# DS12C887.net
KiCad netlist of a schematic drawn in Altium Designer
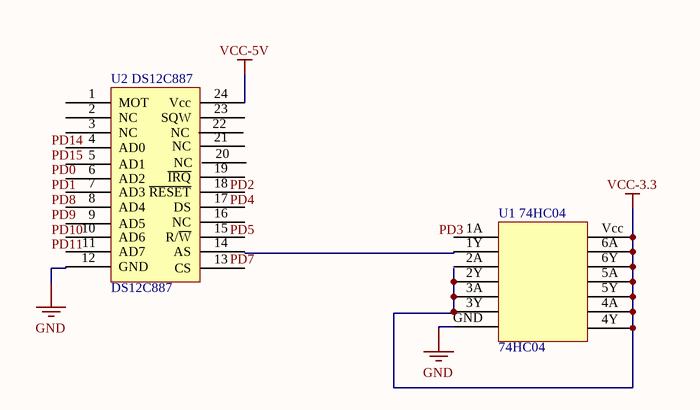
[diagram p0: DS12C887.SchDoc]

(export (version "E")
  (design (tool "Eeschema 10.0.6"))
  (components
    (comp (ref "U1 74HC04") (value "74HC04") (libsource (lib "Schlib1") (part "74HC04")))
    (comp (ref "U2 DS12C887") (value "DS12C887") (libsource (lib "Schlib1") (part "DS12C887")))
  )
  (nets
    (net (code "14") (name "GND") (class "Default")
      (node (ref "U1 74HC04") (pin "GND") (pinfunction "7_GND") (pintype "passive"))
      (node (ref "U2 DS12C887") (pin "12") (pinfunction "GND_12") (pintype "passive"))
    )
    (net (code "15") (name "VCC-3.3") (class "Default")
      (node (ref "U1 74HC04") (pin "2Y") (pinfunction "4_2Y") (pintype "passive"))
      (node (ref "U1 74HC04") (pin "3A") (pinfunction "5_3A") (pintype "passive"))
      (node (ref "U1 74HC04") (pin "3Y") (pinfunction "6_3Y") (pintype "passive"))
      (node (ref "U1 74HC04") (pin "4A") (pinfunction "9_4A") (pintype "passive"))
      (node (ref "U1 74HC04") (pin "4Y") (pinfunction "8_4Y") (pintype "passive"))
      (node (ref "U1 74HC04") (pin "5A") (pinfunction "11_5A") (pintype "passive"))
      (node (ref "U1 74HC04") (pin "5Y") (pinfunction "10_5Y") (pintype "passive"))
      (node (ref "U1 74HC04") (pin "6A") (pinfunction "13_6A") (pintype "passive"))
      (node (ref "U1 74HC04") (pin "6Y") (pinfunction "12_6Y") (pintype "passive"))
      (node (ref "U1 74HC04") (pin "Vcc") (pinfunction "14_Vcc") (pintype "passive"))
    )
    (net (code "16") (name "VCC-5V") (class "Default")
      (node (ref "U2 DS12C887") (pin "24") (pinfunction "Vcc_24") (pintype "passive"))
    )
    (net (code "17") (name "unconnected-(U1 74HC04-1-Pad1A)") (class "Default")
      (node (ref "U1 74HC04") (pin "1A") (pinfunction "1_1A") (pintype "passive"))
    )
    (net (code "18") (name "unconnected-(U1 74HC04-2-Pad1Y)") (class "Default")
      (node (ref "U1 74HC04") (pin "1Y") (pinfunction "2_1Y") (pintype "passive"))
    )
    (net (code "19") (name "unconnected-(U1 74HC04-3-Pad2A)") (class "Default")
      (node (ref "U1 74HC04") (pin "2A") (pinfunction "3_2A") (pintype "passive"))
    )
    (net (code "20") (name "unconnected-(U2 DS12C887-AD0-Pad4)") (class "Default")
      (node (ref "U2 DS12C887") (pin "4") (pinfunction "AD0_4") (pintype "passive"))
    )
    (net (code "21") (name "unconnected-(U2 DS12C887-AD1-Pad5)") (class "Default")
      (node (ref "U2 DS12C887") (pin "5") (pinfunction "AD1_5") (pintype "passive"))
    )
    (net (code "22") (name "unconnected-(U2 DS12C887-AD2-Pad6)") (class "Default")
      (node (ref "U2 DS12C887") (pin "6") (pinfunction "AD2_6") (pintype "passive"))
    )
    (net (code "23") (name "unconnected-(U2 DS12C887-AD3-Pad7)") (class "Default")
      (node (ref "U2 DS12C887") (pin "7") (pinfunction "AD3_7") (pintype "passive"))
    )
    (net (code "24") (name "unconnected-(U2 DS12C887-AD4-Pad8)") (class "Default")
      (node (ref "U2 DS12C887") (pin "8") (pinfunction "AD4_8") (pintype "passive"))
    )
    (net (code "25") (name "unconnected-(U2 DS12C887-AD5-Pad9)") (class "Default")
      (node (ref "U2 DS12C887") (pin "9") (pinfunction "AD5_9") (pintype "passive"))
    )
    (net (code "26") (name "unconnected-(U2 DS12C887-AD6-Pad10)") (class "Default")
      (node (ref "U2 DS12C887") (pin "10") (pinfunction "AD6_10") (pintype "passive"))
    )
    (net (code "27") (name "unconnected-(U2 DS12C887-AD7-Pad11)") (class "Default")
      (node (ref "U2 DS12C887") (pin "11") (pinfunction "AD7_11") (pintype "passive"))
    )
    (net (code "28") (name "unconnected-(U2 DS12C887-AS-Pad14)") (class "Default")
      (node (ref "U2 DS12C887") (pin "14") (pinfunction "AS_14") (pintype "passive"))
    )
    (net (code "29") (name "unconnected-(U2 DS12C887-CS-Pad13)") (class "Default")
      (node (ref "U2 DS12C887") (pin "13") (pinfunction "CS_13") (pintype "passive"))
    )
    (net (code "30") (name "unconnected-(U2 DS12C887-DS-Pad17)") (class "Default")
      (node (ref "U2 DS12C887") (pin "17") (pinfunction "DS_17") (pintype "passive"))
    )
    (net (code "31") (name "unconnected-(U2 DS12C887-MOT-Pad1)") (class "Default")
      (node (ref "U2 DS12C887") (pin "1") (pinfunction "MOT_1") (pintype "passive"))
    )
    (net (code "32") (name "unconnected-(U2 DS12C887-NC-Pad2)") (class "Default")
      (node (ref "U2 DS12C887") (pin "2") (pinfunction "NC_2") (pintype "passive"))
    )
    (net (code "33") (name "unconnected-(U2 DS12C887-NC-Pad3)") (class "Default")
      (node (ref "U2 DS12C887") (pin "3") (pinfunction "NC_3") (pintype "passive"))
    )
    (net (code "34") (name "unconnected-(U2 DS12C887-NC-Pad16)") (class "Default")
      (node (ref "U2 DS12C887") (pin "16") (pinfunction "NC_16") (pintype "passive"))
    )
    (net (code "35") (name "unconnected-(U2 DS12C887-NC-Pad20)") (class "Default")
      (node (ref "U2 DS12C887") (pin "20") (pinfunction "NC_20") (pintype "passive"))
    )
    (net (code "36") (name "unconnected-(U2 DS12C887-NC-Pad21)") (class "Default")
      (node (ref "U2 DS12C887") (pin "21") (pinfunction "NC_21") (pintype "passive"))
    )
    (net (code "37") (name "unconnected-(U2 DS12C887-NC-Pad22)") (class "Default")
      (node (ref "U2 DS12C887") (pin "22") (pinfunction "NC_22") (pintype "passive"))
    )
    (net (code "38") (name "unconnected-(U2 DS12C887-R{slash}~{W}-Pad15)") (class "Default")
      (node (ref "U2 DS12C887") (pin "15") (pinfunction "R/~{W}_15") (pintype "passive"))
    )
    (net (code "39") (name "unconnected-(U2 DS12C887-SQW-Pad23)") (class "Default")
      (node (ref "U2 DS12C887") (pin "23") (pinfunction "SQW_23") (pintype "passive"))
    )
    (net (code "40") (name "unconnected-(U2 DS12C887-~{IRQ}-Pad19)") (class "Default")
      (node (ref "U2 DS12C887") (pin "19") (pinfunction "~{IRQ}_19") (pintype "passive"))
    )
    (net (code "41") (name "unconnected-(U2 DS12C887-~{RESET}-Pad18)") (class "Default")
      (node (ref "U2 DS12C887") (pin "18") (pinfunction "~{RESET}_18") (pintype "passive"))
    )
  )
)
